# analog_inputs_not_isolated.net
KiCad netlist of a schematic drawn in Altium Designer
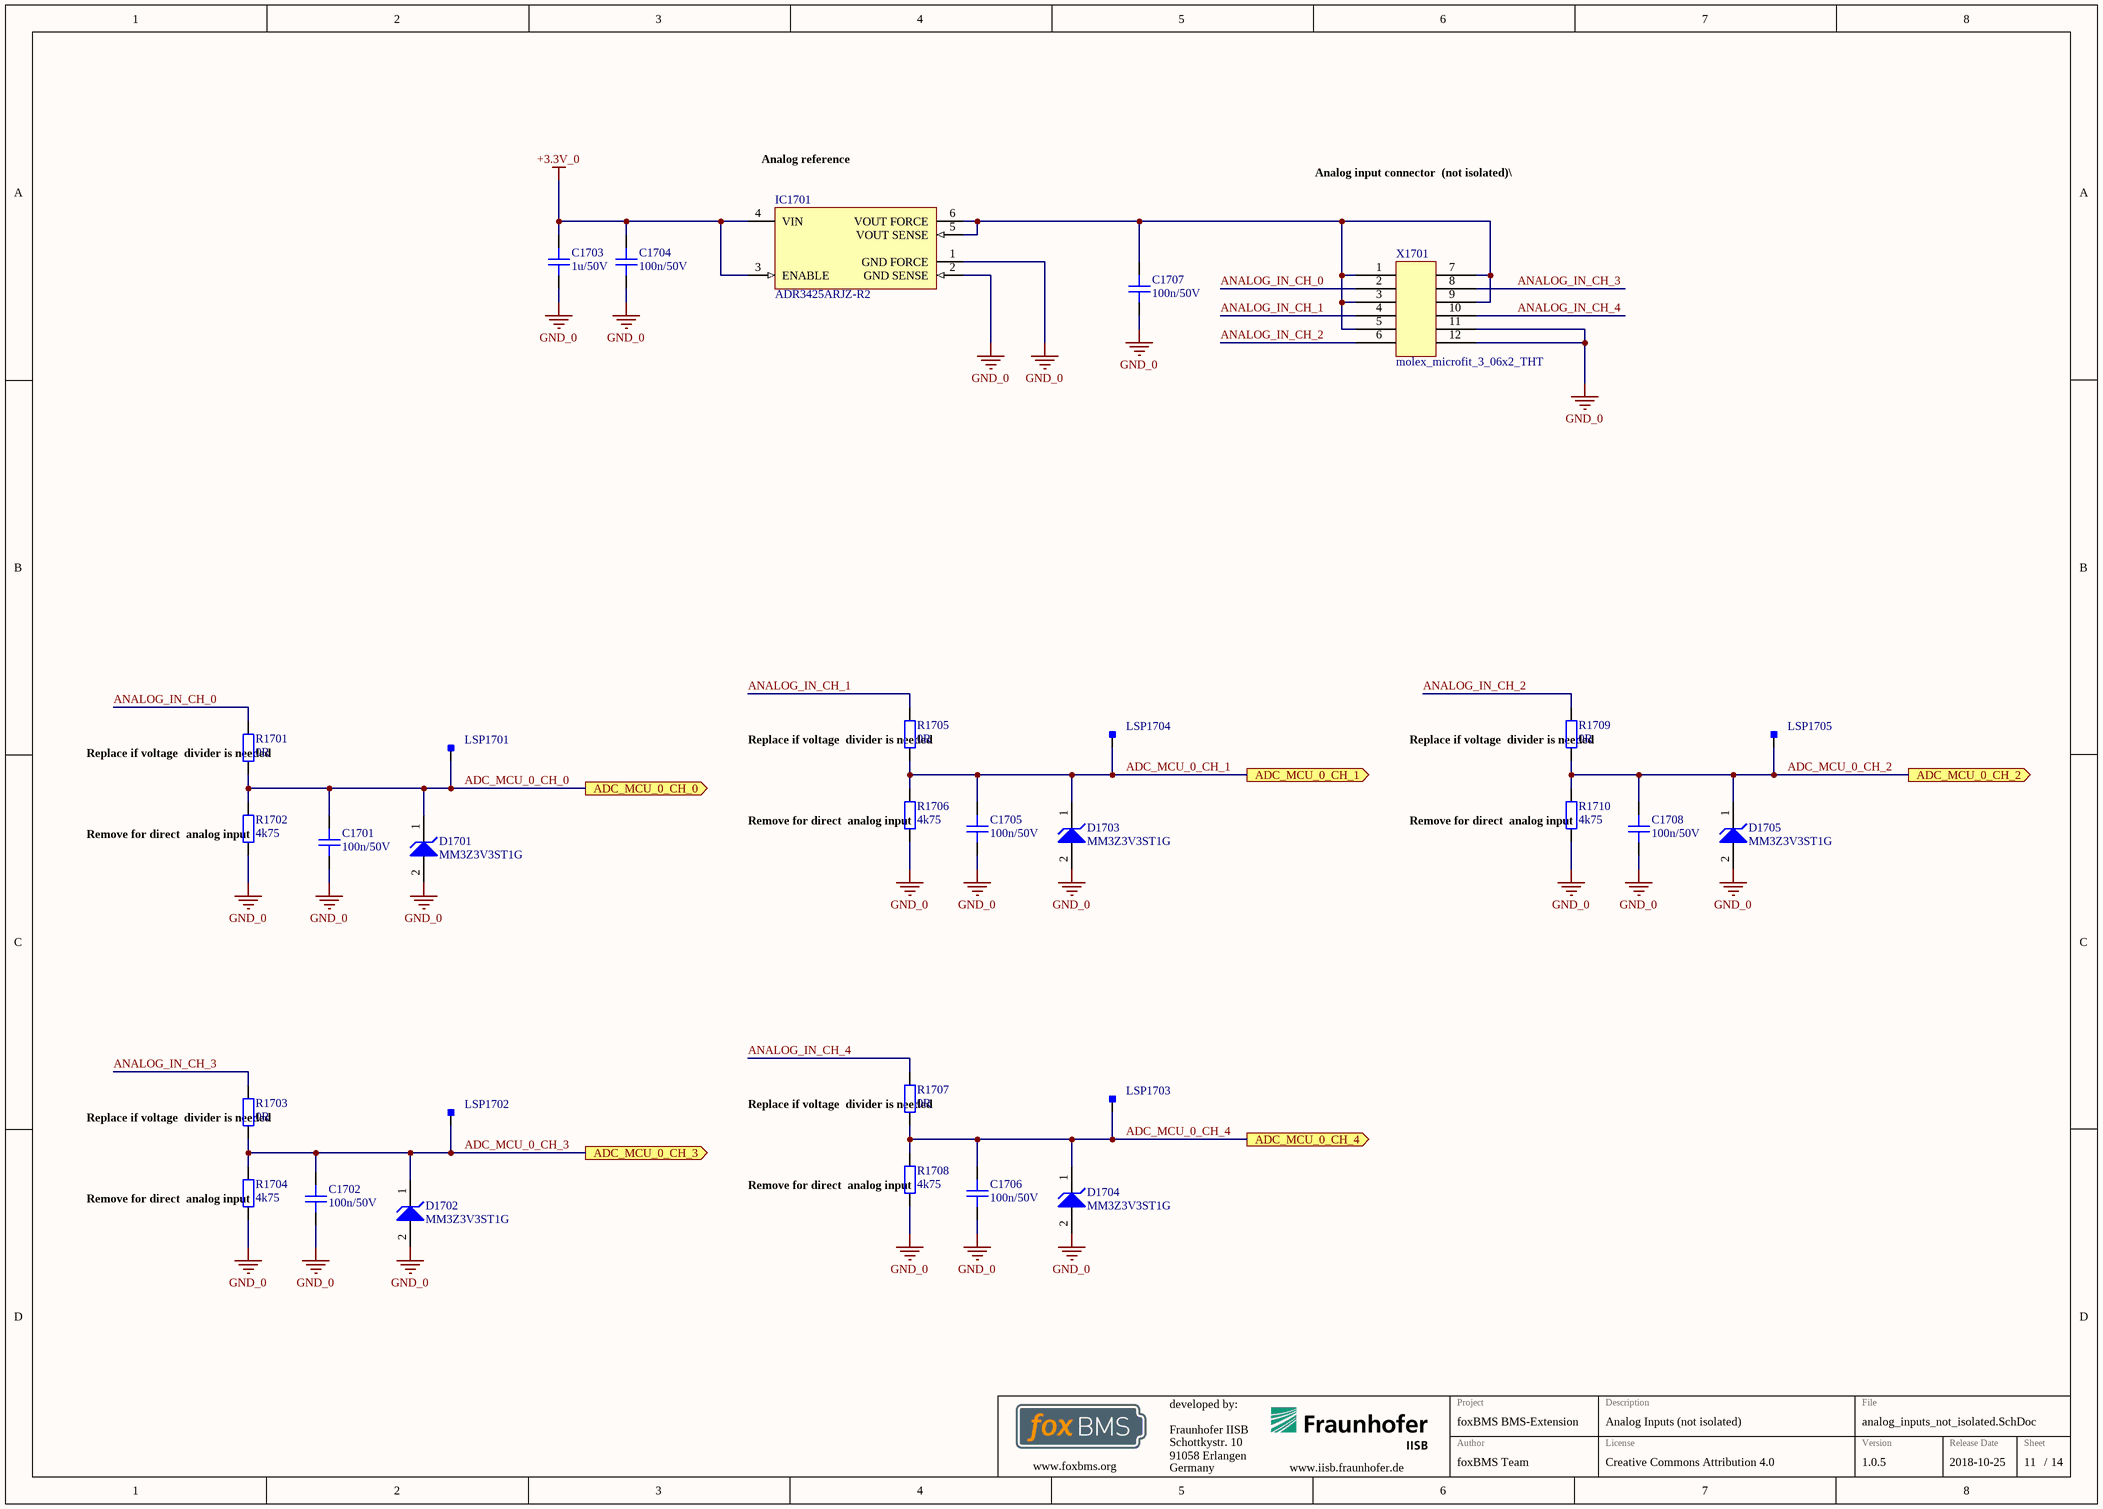
[diagram p0: analog_inputs_not_isolated.SchDoc]

(export (version "E")
  (design (tool "Eeschema 10.0.6"))
  (components
    (comp (ref "C1701")
      (value "100n/50V")
      (footprint "CAPC1608X08N")
      (description "MLCC")
      (fields (field (name "PART NUMBER") "gen_C_ceramic_100n_50V_X7R_0603"))
      (libsource (lib "OE750") (part "C"))
    )
    (comp (ref "C1702")
      (value "100n/50V")
      (footprint "CAPC1608X08N")
      (description "MLCC")
      (fields (field (name "PART NUMBER") "gen_C_ceramic_100n_50V_X7R_0603"))
      (libsource (lib "OE750") (part "C"))
    )
    (comp (ref "C1703")
      (value "1u/50V")
      (footprint "CAPC1608X08N")
      (description "MLCC")
      (fields (field (name "PART NUMBER") "gen_C_ceramic_1u_50V_X7R_0603") (field (name "TOLERANCE") "± 10%"))
      (libsource (lib "OE750") (part "C"))
    )
    (comp (ref "C1704")
      (value "100n/50V")
      (footprint "CAPC1608X08N")
      (description "MLCC")
      (fields (field (name "PART NUMBER") "gen_C_ceramic_100n_50V_X7R_0603"))
      (libsource (lib "OE750") (part "C"))
    )
    (comp (ref "C1705")
      (value "100n/50V")
      (footprint "CAPC1608X08N")
      (description "MLCC")
      (fields (field (name "PART NUMBER") "gen_C_ceramic_100n_50V_X7R_0603"))
      (libsource (lib "OE750") (part "C"))
    )
    (comp (ref "C1706")
      (value "100n/50V")
      (footprint "CAPC1608X08N")
      (description "MLCC")
      (fields (field (name "PART NUMBER") "gen_C_ceramic_100n_50V_X7R_0603"))
      (libsource (lib "OE750") (part "C"))
    )
    (comp (ref "C1707")
      (value "100n/50V")
      (footprint "CAPC1608X08N")
      (description "MLCC")
      (fields (field (name "PART NUMBER") "gen_C_ceramic_100n_50V_X7R_0603"))
      (libsource (lib "OE750") (part "C"))
    )
    (comp (ref "C1708")
      (value "100n/50V")
      (footprint "CAPC1608X08N")
      (description "MLCC")
      (fields (field (name "PART NUMBER") "gen_C_ceramic_100n_50V_X7R_0603"))
      (libsource (lib "OE750") (part "C"))
    )
    (comp (ref "D1701")
      (value "MM3Z3V3ST1G")
      (footprint "ONSC-SOD-323-2-477-02_V")
      (description "Zener Voltage Regulator, 300 mW, Tight Tolerance Portfolio, 2-Pin SOD-323, Pb-Free, Tape and Reel")
      (fields (field (name "MANUFACTURER") "On Semiconductor"))
      (libsource (lib "Altium Content Vault") (part "ONSC-K1A2-2"))
    )
    (comp (ref "D1702")
      (value "MM3Z3V3ST1G")
      (footprint "ONSC-SOD-323-2-477-02_V")
      (description "Zener Voltage Regulator, 300 mW, Tight Tolerance Portfolio, 2-Pin SOD-323, Pb-Free, Tape and Reel")
      (fields (field (name "MANUFACTURER") "On Semiconductor"))
      (libsource (lib "Altium Content Vault") (part "ONSC-K1A2-2"))
    )
    (comp (ref "D1703")
      (value "MM3Z3V3ST1G")
      (footprint "ONSC-SOD-323-2-477-02_V")
      (description "Zener Voltage Regulator, 300 mW, Tight Tolerance Portfolio, 2-Pin SOD-323, Pb-Free, Tape and Reel")
      (fields (field (name "MANUFACTURER") "On Semiconductor"))
      (libsource (lib "Altium Content Vault") (part "ONSC-K1A2-2"))
    )
    (comp (ref "D1704")
      (value "MM3Z3V3ST1G")
      (footprint "ONSC-SOD-323-2-477-02_V")
      (description "Zener Voltage Regulator, 300 mW, Tight Tolerance Portfolio, 2-Pin SOD-323, Pb-Free, Tape and Reel")
      (fields (field (name "MANUFACTURER") "On Semiconductor"))
      (libsource (lib "Altium Content Vault") (part "ONSC-K1A2-2"))
    )
    (comp (ref "D1705")
      (value "MM3Z3V3ST1G")
      (footprint "ONSC-SOD-323-2-477-02_V")
      (description "Zener Voltage Regulator, 300 mW, Tight Tolerance Portfolio, 2-Pin SOD-323, Pb-Free, Tape and Reel")
      (fields (field (name "MANUFACTURER") "On Semiconductor"))
      (libsource (lib "Altium Content Vault") (part "ONSC-K1A2-2"))
    )
    (comp (ref "IC1701")
      (value "ADR3425ARJZ-R2")
      (footprint "ADI-RJ-6_N")
      (fields (field (name "MANUFACTURER") "Analog Devices"))
      (libsource (lib "Altium Content Vault") (part "ADI-ADR34xx-RJ-6"))
    )
    (comp (ref "LSP1701")
      (value "Testpoint_Square")
      (footprint "Testpoint_S1")
      (description "Testpoint, square")
      (libsource (lib "OE750") (part "Testpoint_Square"))
    )
    (comp (ref "LSP1702")
      (value "Testpoint_Square")
      (footprint "Testpoint_S1")
      (description "Testpoint, square")
      (libsource (lib "OE750") (part "Testpoint_Square"))
    )
    (comp (ref "LSP1703")
      (value "Testpoint_Square")
      (footprint "Testpoint_S1")
      (description "Testpoint, square")
      (libsource (lib "OE750") (part "Testpoint_Square"))
    )
    (comp (ref "LSP1704")
      (value "Testpoint_Square")
      (footprint "Testpoint_S1")
      (description "Testpoint, square")
      (libsource (lib "OE750") (part "Testpoint_Square"))
    )
    (comp (ref "LSP1705")
      (value "Testpoint_Square")
      (footprint "Testpoint_S1")
      (description "Testpoint, square")
      (libsource (lib "OE750") (part "Testpoint_Square"))
    )
    (comp (ref "R1701")
      (value "0R")
      (footprint "RESC1608X05N")
      (description "SMD Resistor 0R 0603")
      (fields (field (name "PART NUMBER") "gen_R_0R_0603") (field (name "POWER") "0.1W"))
      (libsource (lib "OE750") (part "R"))
    )
    (comp (ref "R1702")
      (value "4k75")
      (footprint "RESC1608X05N")
      (description "SMD Resistor 4k75 0603")
      (fields (field (name "PART NUMBER") "gen_R_4k75_0603") (field (name "TOLERANCE") "1%"))
      (libsource (lib "OE750") (part "R"))
    )
    (comp (ref "R1703")
      (value "0R")
      (footprint "RESC1608X05N")
      (description "SMD Resistor 0R 0603")
      (fields (field (name "PART NUMBER") "gen_R_0R_0603") (field (name "POWER") "0.1W"))
      (libsource (lib "OE750") (part "R"))
    )
    (comp (ref "R1704")
      (value "4k75")
      (footprint "RESC1608X05N")
      (description "SMD Resistor 4k75 0603")
      (fields (field (name "PART NUMBER") "gen_R_4k75_0603") (field (name "TOLERANCE") "1%"))
      (libsource (lib "OE750") (part "R"))
    )
    (comp (ref "R1705")
      (value "0R")
      (footprint "RESC1608X05N")
      (description "SMD Resistor 0R 0603")
      (fields (field (name "PART NUMBER") "gen_R_0R_0603") (field (name "POWER") "0.1W"))
      (libsource (lib "OE750") (part "R"))
    )
    (comp (ref "R1706")
      (value "4k75")
      (footprint "RESC1608X05N")
      (description "SMD Resistor 4k75 0603")
      (fields (field (name "PART NUMBER") "gen_R_4k75_0603") (field (name "TOLERANCE") "1%"))
      (libsource (lib "OE750") (part "R"))
    )
    (comp (ref "R1707")
      (value "0R")
      (footprint "RESC1608X05N")
      (description "SMD Resistor 0R 0603")
      (fields (field (name "PART NUMBER") "gen_R_0R_0603") (field (name "POWER") "0.1W"))
      (libsource (lib "OE750") (part "R"))
    )
    (comp (ref "R1708")
      (value "4k75")
      (footprint "RESC1608X05N")
      (description "SMD Resistor 4k75 0603")
      (fields (field (name "PART NUMBER") "gen_R_4k75_0603") (field (name "TOLERANCE") "1%"))
      (libsource (lib "OE750") (part "R"))
    )
    (comp (ref "R1709")
      (value "0R")
      (footprint "RESC1608X05N")
      (description "SMD Resistor 0R 0603")
      (fields (field (name "PART NUMBER") "gen_R_0R_0603") (field (name "POWER") "0.1W"))
      (libsource (lib "OE750") (part "R"))
    )
    (comp (ref "R1710")
      (value "4k75")
      (footprint "RESC1608X05N")
      (description "SMD Resistor 4k75 0603")
      (fields (field (name "PART NUMBER") "gen_R_4k75_0603") (field (name "TOLERANCE") "1%"))
      (libsource (lib "OE750") (part "R"))
    )
    (comp (ref "X1701")
      (value "molex_microfit_3_06x2_THT")
      (footprint "MOLEX_MICROFIT_06x2_THT")
      (fields (field (name "MANUFACTURER") "Molex"))
      (libsource (lib "OE750") (part "X6x2"))
    )
  )
  (nets
    (net (code "1") (name "+3.3V_0") (class "Default")
      (node (ref "C1703") (pin "1") (pinfunction "1_1") (pintype "passive"))
      (node (ref "C1704") (pin "1") (pinfunction "1_1") (pintype "passive"))
      (node (ref "IC1701") (pin "3") (pinfunction "ENABLE_3") (pintype "input"))
      (node (ref "IC1701") (pin "4") (pinfunction "VIN_4") (pintype "power_in"))
    )
    (net (code "2") (name "/ADC_MCU_0_CH_0") (class "Default")
      (node (ref "C1701") (pin "1") (pinfunction "1_1") (pintype "passive"))
      (node (ref "D1701") (pin "1") (pinfunction "K_1") (pintype "passive"))
      (node (ref "LSP1701") (pin "1") (pinfunction "1_1") (pintype "passive"))
      (node (ref "R1701") (pin "2") (pinfunction "2_2") (pintype "passive"))
      (node (ref "R1702") (pin "1") (pinfunction "1_1") (pintype "passive"))
    )
    (net (code "3") (name "/ADC_MCU_0_CH_1") (class "Default")
      (node (ref "C1705") (pin "1") (pinfunction "1_1") (pintype "passive"))
      (node (ref "D1703") (pin "1") (pinfunction "K_1") (pintype "passive"))
      (node (ref "LSP1704") (pin "1") (pinfunction "1_1") (pintype "passive"))
      (node (ref "R1705") (pin "2") (pinfunction "2_2") (pintype "passive"))
      (node (ref "R1706") (pin "1") (pinfunction "1_1") (pintype "passive"))
    )
    (net (code "4") (name "/ADC_MCU_0_CH_2") (class "Default")
      (node (ref "C1708") (pin "1") (pinfunction "1_1") (pintype "passive"))
      (node (ref "D1705") (pin "1") (pinfunction "K_1") (pintype "passive"))
      (node (ref "LSP1705") (pin "1") (pinfunction "1_1") (pintype "passive"))
      (node (ref "R1709") (pin "2") (pinfunction "2_2") (pintype "passive"))
      (node (ref "R1710") (pin "1") (pinfunction "1_1") (pintype "passive"))
    )
    (net (code "5") (name "/ADC_MCU_0_CH_3") (class "Default")
      (node (ref "C1702") (pin "1") (pinfunction "1_1") (pintype "passive"))
      (node (ref "D1702") (pin "1") (pinfunction "K_1") (pintype "passive"))
      (node (ref "LSP1702") (pin "1") (pinfunction "1_1") (pintype "passive"))
      (node (ref "R1703") (pin "2") (pinfunction "2_2") (pintype "passive"))
      (node (ref "R1704") (pin "1") (pinfunction "1_1") (pintype "passive"))
    )
    (net (code "6") (name "/ADC_MCU_0_CH_4") (class "Default")
      (node (ref "C1706") (pin "1") (pinfunction "1_1") (pintype "passive"))
      (node (ref "D1704") (pin "1") (pinfunction "K_1") (pintype "passive"))
      (node (ref "LSP1703") (pin "1") (pinfunction "1_1") (pintype "passive"))
      (node (ref "R1707") (pin "2") (pinfunction "2_2") (pintype "passive"))
      (node (ref "R1708") (pin "1") (pinfunction "1_1") (pintype "passive"))
    )
    (net (code "7") (name "/ANALOG_IN_CH_0") (class "Default")
      (node (ref "R1701") (pin "1") (pinfunction "1_1") (pintype "passive"))
      (node (ref "X1701") (pin "2") (pintype "passive"))
    )
    (net (code "8") (name "/ANALOG_IN_CH_1") (class "Default")
      (node (ref "R1705") (pin "1") (pinfunction "1_1") (pintype "passive"))
      (node (ref "X1701") (pin "4") (pintype "passive"))
    )
    (net (code "9") (name "/ANALOG_IN_CH_2") (class "Default")
      (node (ref "R1709") (pin "1") (pinfunction "1_1") (pintype "passive"))
      (node (ref "X1701") (pin "6") (pintype "passive"))
    )
    (net (code "10") (name "/ANALOG_IN_CH_3") (class "Default")
      (node (ref "R1703") (pin "1") (pinfunction "1_1") (pintype "passive"))
      (node (ref "X1701") (pin "8") (pintype "passive"))
    )
    (net (code "11") (name "/ANALOG_IN_CH_4") (class "Default")
      (node (ref "R1707") (pin "1") (pinfunction "1_1") (pintype "passive"))
      (node (ref "X1701") (pin "10") (pintype "passive"))
    )
    (net (code "12") (name "GND_0") (class "Default")
      (node (ref "C1701") (pin "2") (pinfunction "2_2") (pintype "passive"))
      (node (ref "C1702") (pin "2") (pinfunction "2_2") (pintype "passive"))
      (node (ref "C1703") (pin "2") (pinfunction "2_2") (pintype "passive"))
      (node (ref "C1704") (pin "2") (pinfunction "2_2") (pintype "passive"))
      (node (ref "C1705") (pin "2") (pinfunction "2_2") (pintype "passive"))
      (node (ref "C1706") (pin "2") (pinfunction "2_2") (pintype "passive"))
      (node (ref "C1707") (pin "2") (pinfunction "2_2") (pintype "passive"))
      (node (ref "C1708") (pin "2") (pinfunction "2_2") (pintype "passive"))
      (node (ref "D1701") (pin "2") (pinfunction "A_2") (pintype "passive"))
      (node (ref "D1702") (pin "2") (pinfunction "A_2") (pintype "passive"))
      (node (ref "D1703") (pin "2") (pinfunction "A_2") (pintype "passive"))
      (node (ref "D1704") (pin "2") (pinfunction "A_2") (pintype "passive"))
      (node (ref "D1705") (pin "2") (pinfunction "A_2") (pintype "passive"))
      (node (ref "IC1701") (pin "1") (pinfunction "GND_FORCE_1") (pintype "power_in"))
      (node (ref "IC1701") (pin "2") (pinfunction "GND_SENSE_2") (pintype "input"))
      (node (ref "R1702") (pin "2") (pinfunction "2_2") (pintype "passive"))
      (node (ref "R1704") (pin "2") (pinfunction "2_2") (pintype "passive"))
      (node (ref "R1706") (pin "2") (pinfunction "2_2") (pintype "passive"))
      (node (ref "R1708") (pin "2") (pinfunction "2_2") (pintype "passive"))
      (node (ref "R1710") (pin "2") (pinfunction "2_2") (pintype "passive"))
      (node (ref "X1701") (pin "11") (pintype "passive"))
      (node (ref "X1701") (pin "12") (pintype "passive"))
    )
    (net (code "13") (name "Net-(IC1701-VOUT_FORCE)") (class "Default")
      (node (ref "C1707") (pin "1") (pinfunction "1_1") (pintype "passive"))
      (node (ref "IC1701") (pin "5") (pinfunction "VOUT_SENSE_5") (pintype "input"))
      (node (ref "IC1701") (pin "6") (pinfunction "VOUT_FORCE_6") (pintype "power_in"))
      (node (ref "X1701") (pin "1") (pintype "passive"))
      (node (ref "X1701") (pin "3") (pintype "passive"))
      (node (ref "X1701") (pin "5") (pintype "passive"))
      (node (ref "X1701") (pin "7") (pintype "passive"))
      (node (ref "X1701") (pin "9") (pintype "passive"))
    )
  )
)
